# SPDIF.net
KiCad netlist of a schematic drawn in Altium Designer
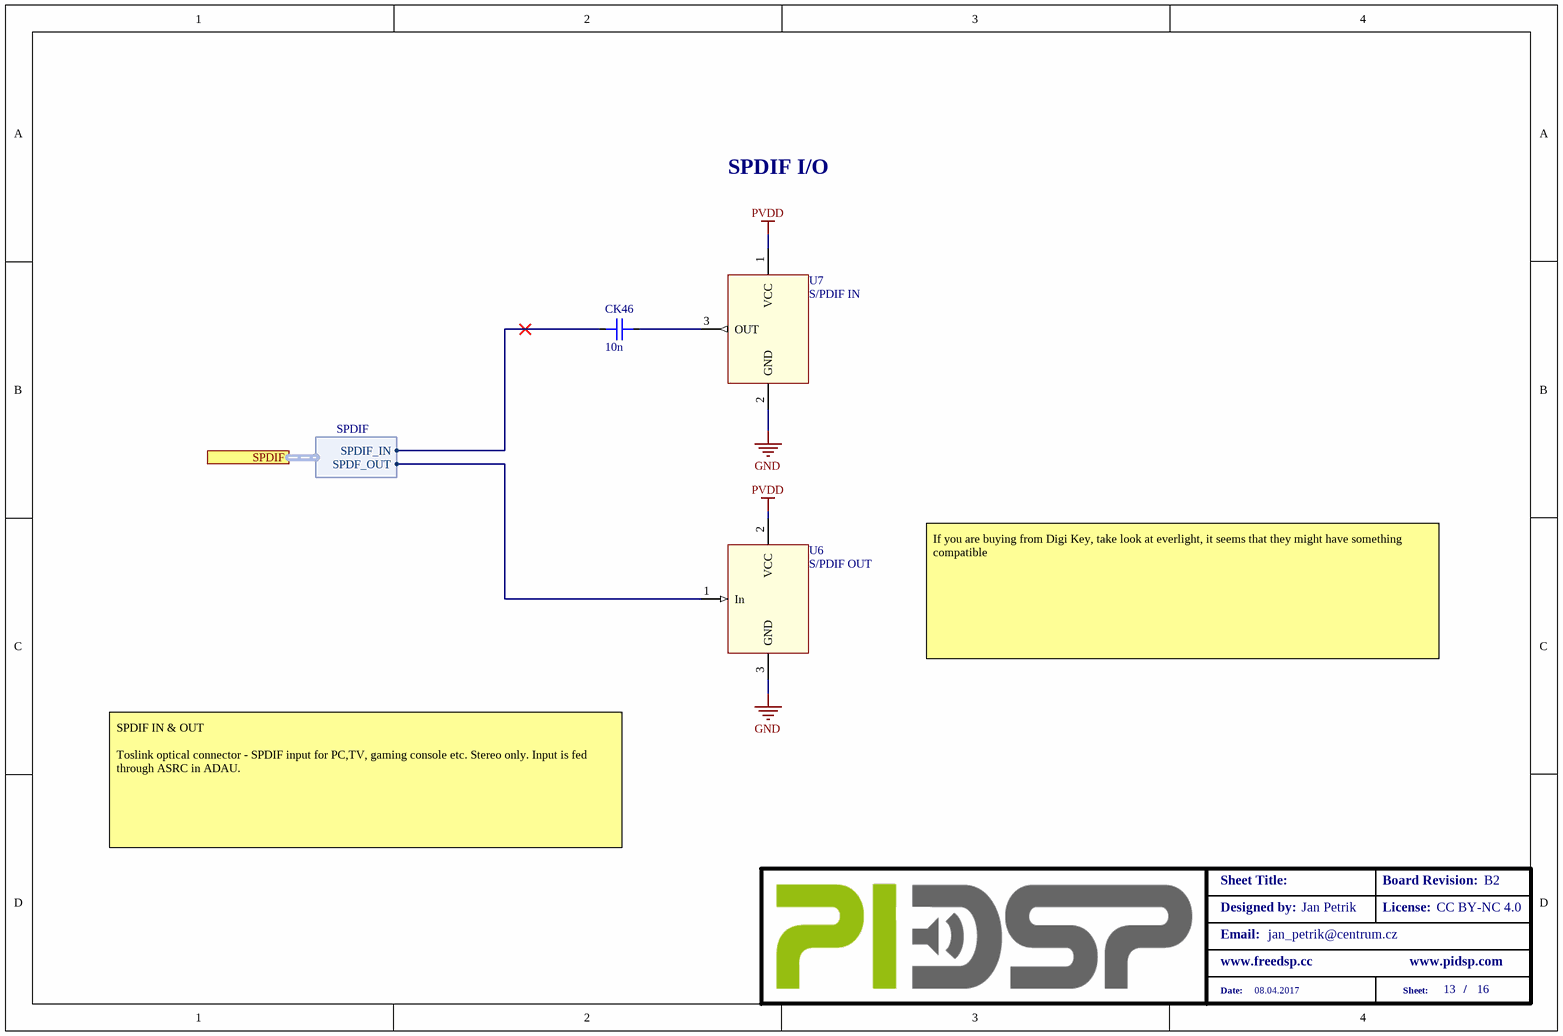
[diagram p0: SPDIF.SchDoc]

(export (version "E")
  (design (tool "Eeschema 10.0.6"))
  (components
    (comp (ref "CK46")
      (value "10n")
      (footprint "CAPC1608X09N(SMC0603)")
      (description "MLCC")
      (fields
        (field (name "TOLERANCE") "10%")
        (field (name "VOLTAGE") "50V")
        (field (name "AUTHOR") "JP/27.03.2014")
      )
      (libsource (lib "JP_C") (part "10n-50V-0603-X7R"))
    )
    (comp (ref "U6")
      (value "S/PDIF OUT")
      (footprint "OTJ/ORJ 8")
      (description "Toslink Transmitter")
      (libsource (lib "JP_IC") (part "OTJ-8"))
    )
    (comp (ref "U7")
      (value "S/PDIF IN")
      (footprint "OTJ/ORJ 8")
      (description "Toslink Reciever")
      (libsource (lib "JP_IC") (part "ORJ-8"))
    )
  )
  (nets
    (net (code "2") (name "/SPDF_OUT") (class "Default")
      (node (ref "U6") (pin "1") (pinfunction "In_1") (pintype "input"))
    )
    (net (code "3") (name "/SPDIF_IN") (class "Default")
      (node (ref "CK46") (pin "2") (pinfunction "2_2") (pintype "passive"))
    )
    (net (code "5") (name "GND") (class "Default")
      (node (ref "U6") (pin "3") (pinfunction "GND_3") (pintype "passive"))
      (node (ref "U7") (pin "2") (pinfunction "GND_2") (pintype "passive"))
    )
    (net (code "6") (name "Net-(U7-OUT)") (class "Default")
      (node (ref "CK46") (pin "1") (pinfunction "1_1") (pintype "passive"))
      (node (ref "U7") (pin "3") (pinfunction "OUT_3") (pintype "output"))
    )
    (net (code "7") (name "PVDD") (class "Default")
      (node (ref "U6") (pin "2") (pinfunction "VCC_2") (pintype "passive"))
      (node (ref "U7") (pin "1") (pinfunction "VCC_1") (pintype "passive"))
    )
  )
)
